# Top.net
KiCad netlist of a schematic drawn in Altium Designer
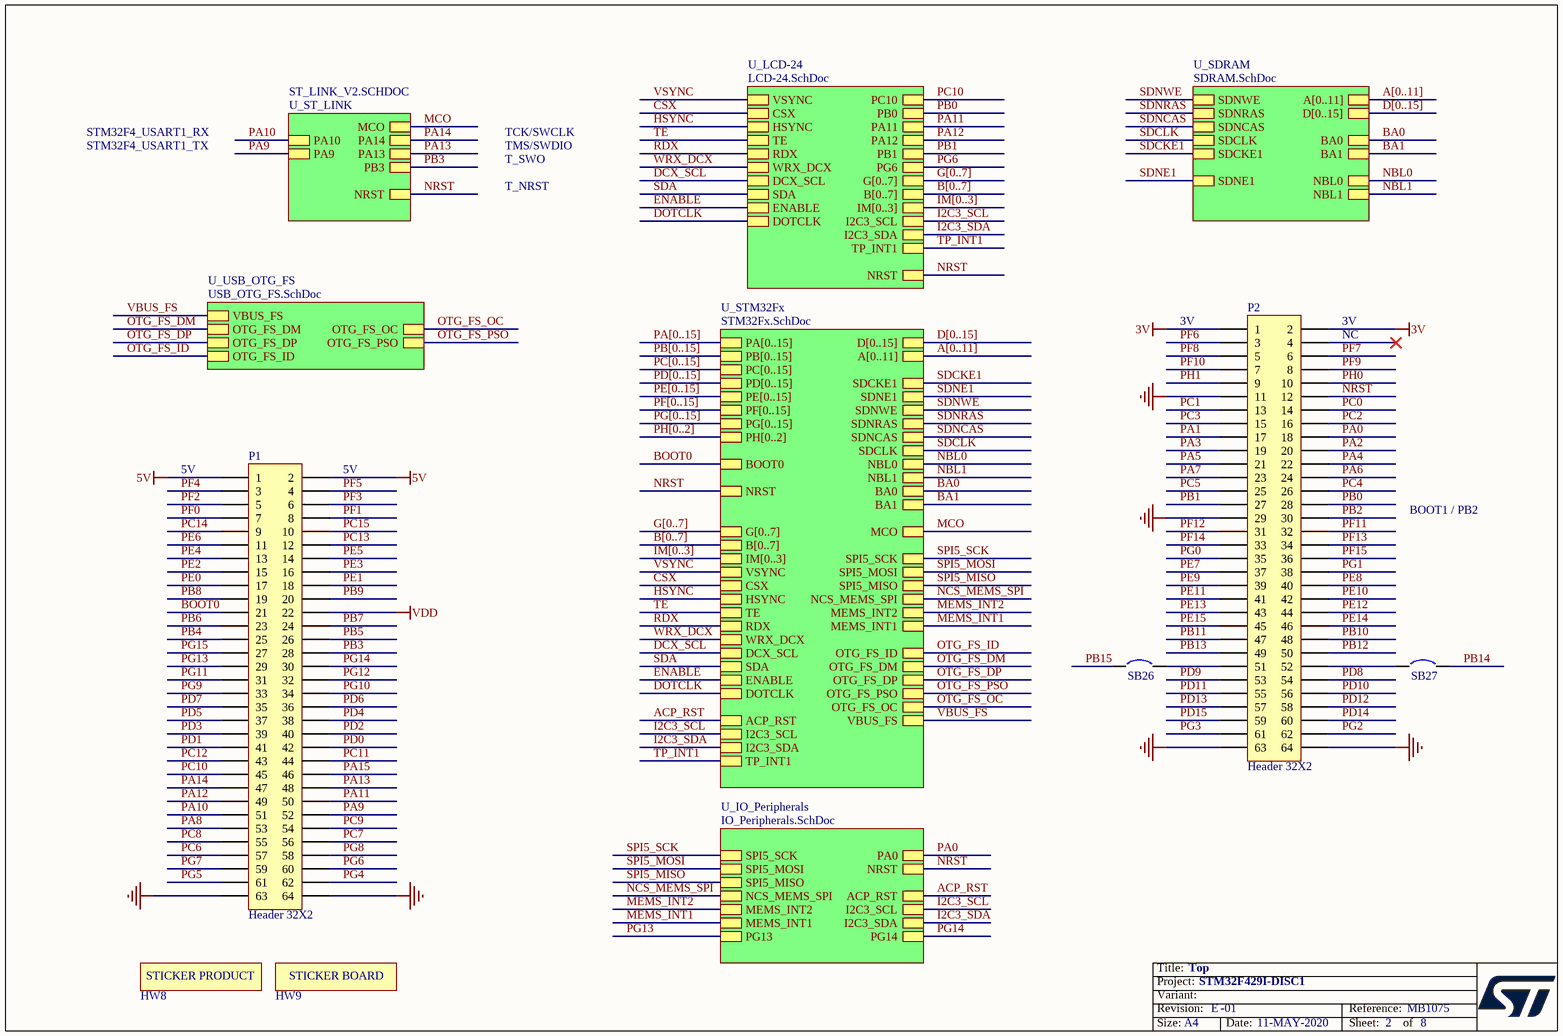
[diagram p0: Top.SchDoc]

(export (version "E")
  (design (tool "Eeschema 10.0.6"))
  (components
    (comp (ref "HW8") (value "STICKER_PRODUCT") (libsource (lib "MB1075") (part "STICKER_PRODUCT")))
    (comp (ref "HW9") (value "STICKER_BOARD") (libsource (lib "MB1075") (part "STICKER_BOARD")))
    (comp (ref "P1")
      (value "Header 32X2")
      (footprint "HDR2X32")
      (description "Header, 32-Pin, Dual row")
      (fields (field (name "PUBLISHER") "Altium Limited"))
      (libsource (lib "MCD_TOOLS") (part "Header 32X2"))
    )
    (comp (ref "P2")
      (value "Header 32X2")
      (footprint "HDR2X32")
      (description "Header, 32-Pin, Dual row")
      (fields (field (name "PUBLISHER") "Altium Limited"))
      (libsource (lib "MCD_TOOLS") (part "Header 32X2"))
    )
    (comp (ref "SB26")
      (value "Circuit Breaker")
      (footprint "JP2_SMD")
      (fields (field (name "PUBLISHER") "Altium Limited"))
      (libsource (lib "MCD_TOOLS") (part "Circuit Breaker"))
    )
    (comp (ref "SB27")
      (value "Circuit Breaker")
      (footprint "JP2_SMD")
      (fields (field (name "PUBLISHER") "Altium Limited"))
      (libsource (lib "MCD_TOOLS") (part "Circuit Breaker"))
    )
  )
  (nets
    (net (code "54") (name "/BOOT0") (class "Default")
      (node (ref "P1") (pin "21") (pinfunction "21_21") (pintype "passive"))
    )
    (net (code "72") (name "/NRST") (class "Default")
      (node (ref "P2") (pin "12") (pinfunction "12_12") (pintype "passive"))
    )
    (net (code "78") (name "/PA0") (class "Default")
      (node (ref "P2") (pin "18") (pinfunction "18_18") (pintype "passive"))
    )
    (net (code "79") (name "/PA1") (class "Default")
      (node (ref "P2") (pin "17") (pinfunction "17_17") (pintype "passive"))
    )
    (net (code "80") (name "/PA2") (class "Default")
      (node (ref "P2") (pin "20") (pinfunction "20_20") (pintype "passive"))
    )
    (net (code "81") (name "/PA3") (class "Default")
      (node (ref "P2") (pin "19") (pinfunction "19_19") (pintype "passive"))
    )
    (net (code "82") (name "/PA4") (class "Default")
      (node (ref "P2") (pin "22") (pinfunction "22_22") (pintype "passive"))
    )
    (net (code "83") (name "/PA5") (class "Default")
      (node (ref "P2") (pin "21") (pinfunction "21_21") (pintype "passive"))
    )
    (net (code "84") (name "/PA6") (class "Default")
      (node (ref "P2") (pin "24") (pinfunction "24_24") (pintype "passive"))
    )
    (net (code "85") (name "/PA7") (class "Default")
      (node (ref "P2") (pin "23") (pinfunction "23_23") (pintype "passive"))
    )
    (net (code "86") (name "/PA8") (class "Default")
      (node (ref "P1") (pin "53") (pinfunction "53_53") (pintype "passive"))
    )
    (net (code "87") (name "/PA9") (class "Default")
      (node (ref "P1") (pin "52") (pinfunction "52_52") (pintype "passive"))
    )
    (net (code "88") (name "/PA10") (class "Default")
      (node (ref "P1") (pin "51") (pinfunction "51_51") (pintype "passive"))
    )
    (net (code "89") (name "/PA11") (class "Default")
      (node (ref "P1") (pin "50") (pinfunction "50_50") (pintype "passive"))
    )
    (net (code "90") (name "/PA12") (class "Default")
      (node (ref "P1") (pin "49") (pinfunction "49_49") (pintype "passive"))
    )
    (net (code "91") (name "/PA13") (class "Default")
      (node (ref "P1") (pin "48") (pinfunction "48_48") (pintype "passive"))
    )
    (net (code "92") (name "/PA14") (class "Default")
      (node (ref "P1") (pin "47") (pinfunction "47_47") (pintype "passive"))
    )
    (net (code "93") (name "/PA15") (class "Default")
      (node (ref "P1") (pin "46") (pinfunction "46_46") (pintype "passive"))
    )
    (net (code "95") (name "/PB0") (class "Default")
      (node (ref "P2") (pin "28") (pinfunction "28_28") (pintype "passive"))
    )
    (net (code "96") (name "/PB1") (class "Default")
      (node (ref "P2") (pin "27") (pinfunction "27_27") (pintype "passive"))
    )
    (net (code "97") (name "/PB2") (class "Default")
      (node (ref "P2") (pin "30") (pinfunction "30_30") (pintype "passive"))
    )
    (net (code "98") (name "/PB3") (class "Default")
      (node (ref "P1") (pin "28") (pinfunction "28_28") (pintype "passive"))
    )
    (net (code "99") (name "/PB4") (class "Default")
      (node (ref "P1") (pin "25") (pinfunction "25_25") (pintype "passive"))
    )
    (net (code "100") (name "/PB5") (class "Default")
      (node (ref "P1") (pin "26") (pinfunction "26_26") (pintype "passive"))
    )
    (net (code "101") (name "/PB6") (class "Default")
      (node (ref "P1") (pin "23") (pinfunction "23_23") (pintype "passive"))
    )
    (net (code "102") (name "/PB7") (class "Default")
      (node (ref "P1") (pin "24") (pinfunction "24_24") (pintype "passive"))
    )
    (net (code "103") (name "/PB8") (class "Default")
      (node (ref "P1") (pin "19") (pinfunction "19_19") (pintype "passive"))
    )
    (net (code "104") (name "/PB9") (class "Default")
      (node (ref "P1") (pin "20") (pinfunction "20_20") (pintype "passive"))
    )
    (net (code "105") (name "/PB10") (class "Default")
      (node (ref "P2") (pin "48") (pinfunction "48_48") (pintype "passive"))
    )
    (net (code "106") (name "/PB11") (class "Default")
      (node (ref "P2") (pin "47") (pinfunction "47_47") (pintype "passive"))
    )
    (net (code "107") (name "/PB12") (class "Default")
      (node (ref "P2") (pin "50") (pinfunction "50_50") (pintype "passive"))
    )
    (net (code "108") (name "/PB13") (class "Default")
      (node (ref "P2") (pin "49") (pinfunction "49_49") (pintype "passive"))
    )
    (net (code "109") (name "/PB14") (class "Default")
      (node (ref "SB27") (pin "2") (pinfunction "2_2") (pintype "passive"))
    )
    (net (code "110") (name "/PB15") (class "Default")
      (node (ref "SB26") (pin "1") (pinfunction "1_1") (pintype "passive"))
    )
    (net (code "112") (name "/PC0") (class "Default")
      (node (ref "P2") (pin "14") (pinfunction "14_14") (pintype "passive"))
    )
    (net (code "113") (name "/PC1") (class "Default")
      (node (ref "P2") (pin "13") (pinfunction "13_13") (pintype "passive"))
    )
    (net (code "114") (name "/PC2") (class "Default")
      (node (ref "P2") (pin "16") (pinfunction "16_16") (pintype "passive"))
    )
    (net (code "115") (name "/PC3") (class "Default")
      (node (ref "P2") (pin "15") (pinfunction "15_15") (pintype "passive"))
    )
    (net (code "116") (name "/PC4") (class "Default")
      (node (ref "P2") (pin "26") (pinfunction "26_26") (pintype "passive"))
    )
    (net (code "117") (name "/PC5") (class "Default")
      (node (ref "P2") (pin "25") (pinfunction "25_25") (pintype "passive"))
    )
    (net (code "118") (name "/PC6") (class "Default")
      (node (ref "P1") (pin "57") (pinfunction "57_57") (pintype "passive"))
    )
    (net (code "119") (name "/PC7") (class "Default")
      (node (ref "P1") (pin "56") (pinfunction "56_56") (pintype "passive"))
    )
    (net (code "120") (name "/PC8") (class "Default")
      (node (ref "P1") (pin "55") (pinfunction "55_55") (pintype "passive"))
    )
    (net (code "121") (name "/PC9") (class "Default")
      (node (ref "P1") (pin "54") (pinfunction "54_54") (pintype "passive"))
    )
    (net (code "122") (name "/PC10") (class "Default")
      (node (ref "P1") (pin "45") (pinfunction "45_45") (pintype "passive"))
    )
    (net (code "123") (name "/PC11") (class "Default")
      (node (ref "P1") (pin "44") (pinfunction "44_44") (pintype "passive"))
    )
    (net (code "124") (name "/PC12") (class "Default")
      (node (ref "P1") (pin "43") (pinfunction "43_43") (pintype "passive"))
    )
    (net (code "125") (name "/PC13") (class "Default")
      (node (ref "P1") (pin "12") (pinfunction "12_12") (pintype "passive"))
    )
    (net (code "126") (name "/PC14") (class "Default")
      (node (ref "P1") (pin "9") (pinfunction "9_9") (pintype "passive"))
    )
    (net (code "127") (name "/PC15") (class "Default")
      (node (ref "P1") (pin "10") (pinfunction "10_10") (pintype "passive"))
    )
    (net (code "129") (name "/PD0") (class "Default")
      (node (ref "P1") (pin "42") (pinfunction "42_42") (pintype "passive"))
    )
    (net (code "130") (name "/PD1") (class "Default")
      (node (ref "P1") (pin "41") (pinfunction "41_41") (pintype "passive"))
    )
    (net (code "131") (name "/PD2") (class "Default")
      (node (ref "P1") (pin "40") (pinfunction "40_40") (pintype "passive"))
    )
    (net (code "132") (name "/PD3") (class "Default")
      (node (ref "P1") (pin "39") (pinfunction "39_39") (pintype "passive"))
    )
    (net (code "133") (name "/PD4") (class "Default")
      (node (ref "P1") (pin "38") (pinfunction "38_38") (pintype "passive"))
    )
    (net (code "134") (name "/PD5") (class "Default")
      (node (ref "P1") (pin "37") (pinfunction "37_37") (pintype "passive"))
    )
    (net (code "135") (name "/PD6") (class "Default")
      (node (ref "P1") (pin "36") (pinfunction "36_36") (pintype "passive"))
    )
    (net (code "136") (name "/PD7") (class "Default")
      (node (ref "P1") (pin "35") (pinfunction "35_35") (pintype "passive"))
    )
    (net (code "137") (name "/PD8") (class "Default")
      (node (ref "P2") (pin "54") (pinfunction "54_54") (pintype "passive"))
    )
    (net (code "138") (name "/PD9") (class "Default")
      (node (ref "P2") (pin "53") (pinfunction "53_53") (pintype "passive"))
    )
    (net (code "139") (name "/PD10") (class "Default")
      (node (ref "P2") (pin "56") (pinfunction "56_56") (pintype "passive"))
    )
    (net (code "140") (name "/PD11") (class "Default")
      (node (ref "P2") (pin "55") (pinfunction "55_55") (pintype "passive"))
    )
    (net (code "141") (name "/PD12") (class "Default")
      (node (ref "P2") (pin "58") (pinfunction "58_58") (pintype "passive"))
    )
    (net (code "142") (name "/PD13") (class "Default")
      (node (ref "P2") (pin "57") (pinfunction "57_57") (pintype "passive"))
    )
    (net (code "143") (name "/PD14") (class "Default")
      (node (ref "P2") (pin "60") (pinfunction "60_60") (pintype "passive"))
    )
    (net (code "144") (name "/PD15") (class "Default")
      (node (ref "P2") (pin "59") (pinfunction "59_59") (pintype "passive"))
    )
    (net (code "146") (name "/PE0") (class "Default")
      (node (ref "P1") (pin "17") (pinfunction "17_17") (pintype "passive"))
    )
    (net (code "147") (name "/PE1") (class "Default")
      (node (ref "P1") (pin "18") (pinfunction "18_18") (pintype "passive"))
    )
    (net (code "148") (name "/PE2") (class "Default")
      (node (ref "P1") (pin "15") (pinfunction "15_15") (pintype "passive"))
    )
    (net (code "149") (name "/PE3") (class "Default")
      (node (ref "P1") (pin "16") (pinfunction "16_16") (pintype "passive"))
    )
    (net (code "150") (name "/PE4") (class "Default")
      (node (ref "P1") (pin "13") (pinfunction "13_13") (pintype "passive"))
    )
    (net (code "151") (name "/PE5") (class "Default")
      (node (ref "P1") (pin "14") (pinfunction "14_14") (pintype "passive"))
    )
    (net (code "152") (name "/PE6") (class "Default")
      (node (ref "P1") (pin "11") (pinfunction "11_11") (pintype "passive"))
    )
    (net (code "153") (name "/PE7") (class "Default")
      (node (ref "P2") (pin "37") (pinfunction "37_37") (pintype "passive"))
    )
    (net (code "154") (name "/PE8") (class "Default")
      (node (ref "P2") (pin "40") (pinfunction "40_40") (pintype "passive"))
    )
    (net (code "155") (name "/PE9") (class "Default")
      (node (ref "P2") (pin "39") (pinfunction "39_39") (pintype "passive"))
    )
    (net (code "156") (name "/PE10") (class "Default")
      (node (ref "P2") (pin "42") (pinfunction "42_42") (pintype "passive"))
    )
    (net (code "157") (name "/PE11") (class "Default")
      (node (ref "P2") (pin "41") (pinfunction "41_41") (pintype "passive"))
    )
    (net (code "158") (name "/PE12") (class "Default")
      (node (ref "P2") (pin "44") (pinfunction "44_44") (pintype "passive"))
    )
    (net (code "159") (name "/PE13") (class "Default")
      (node (ref "P2") (pin "43") (pinfunction "43_43") (pintype "passive"))
    )
    (net (code "160") (name "/PE14") (class "Default")
      (node (ref "P2") (pin "46") (pinfunction "46_46") (pintype "passive"))
    )
    (net (code "161") (name "/PE15") (class "Default")
      (node (ref "P2") (pin "45") (pinfunction "45_45") (pintype "passive"))
    )
    (net (code "163") (name "/PF0") (class "Default")
      (node (ref "P1") (pin "7") (pinfunction "7_7") (pintype "passive"))
    )
    (net (code "164") (name "/PF1") (class "Default")
      (node (ref "P1") (pin "8") (pinfunction "8_8") (pintype "passive"))
    )
    (net (code "165") (name "/PF2") (class "Default")
      (node (ref "P1") (pin "5") (pinfunction "5_5") (pintype "passive"))
    )
    (net (code "166") (name "/PF3") (class "Default")
      (node (ref "P1") (pin "6") (pinfunction "6_6") (pintype "passive"))
    )
    (net (code "167") (name "/PF4") (class "Default")
      (node (ref "P1") (pin "3") (pinfunction "3_3") (pintype "passive"))
    )
    (net (code "168") (name "/PF5") (class "Default")
      (node (ref "P1") (pin "4") (pinfunction "4_4") (pintype "passive"))
    )
    (net (code "169") (name "/PF6") (class "Default")
      (node (ref "P2") (pin "3") (pinfunction "3_3") (pintype "passive"))
    )
    (net (code "170") (name "/PF7") (class "Default")
      (node (ref "P2") (pin "6") (pinfunction "6_6") (pintype "passive"))
    )
    (net (code "171") (name "/PF8") (class "Default")
      (node (ref "P2") (pin "5") (pinfunction "5_5") (pintype "passive"))
    )
    (net (code "172") (name "/PF9") (class "Default")
      (node (ref "P2") (pin "8") (pinfunction "8_8") (pintype "passive"))
    )
    (net (code "173") (name "/PF10") (class "Default")
      (node (ref "P2") (pin "7") (pinfunction "7_7") (pintype "passive"))
    )
    (net (code "174") (name "/PF11") (class "Default")
      (node (ref "P2") (pin "32") (pinfunction "32_32") (pintype "passive"))
    )
    (net (code "175") (name "/PF12") (class "Default")
      (node (ref "P2") (pin "31") (pinfunction "31_31") (pintype "passive"))
    )
    (net (code "176") (name "/PF13") (class "Default")
      (node (ref "P2") (pin "34") (pinfunction "34_34") (pintype "passive"))
    )
    (net (code "177") (name "/PF14") (class "Default")
      (node (ref "P2") (pin "33") (pinfunction "33_33") (pintype "passive"))
    )
    (net (code "178") (name "/PF15") (class "Default")
      (node (ref "P2") (pin "36") (pinfunction "36_36") (pintype "passive"))
    )
    (net (code "180") (name "/PG0") (class "Default")
      (node (ref "P2") (pin "35") (pinfunction "35_35") (pintype "passive"))
    )
    (net (code "181") (name "/PG1") (class "Default")
      (node (ref "P2") (pin "38") (pinfunction "38_38") (pintype "passive"))
    )
    (net (code "182") (name "/PG2") (class "Default")
      (node (ref "P2") (pin "62") (pinfunction "62_62") (pintype "passive"))
    )
    (net (code "183") (name "/PG3") (class "Default")
      (node (ref "P2") (pin "61") (pinfunction "61_61") (pintype "passive"))
    )
    (net (code "184") (name "/PG4") (class "Default")
      (node (ref "P1") (pin "62") (pinfunction "62_62") (pintype "passive"))
    )
    (net (code "185") (name "/PG5") (class "Default")
      (node (ref "P1") (pin "61") (pinfunction "61_61") (pintype "passive"))
    )
    (net (code "186") (name "/PG6") (class "Default")
      (node (ref "P1") (pin "60") (pinfunction "60_60") (pintype "passive"))
    )
    (net (code "187") (name "/PG7") (class "Default")
      (node (ref "P1") (pin "59") (pinfunction "59_59") (pintype "passive"))
    )
    (net (code "188") (name "/PG8") (class "Default")
      (node (ref "P1") (pin "58") (pinfunction "58_58") (pintype "passive"))
    )
    (net (code "189") (name "/PG9") (class "Default")
      (node (ref "P1") (pin "33") (pinfunction "33_33") (pintype "passive"))
    )
    (net (code "190") (name "/PG10") (class "Default")
      (node (ref "P1") (pin "34") (pinfunction "34_34") (pintype "passive"))
    )
    (net (code "191") (name "/PG11") (class "Default")
      (node (ref "P1") (pin "31") (pinfunction "31_31") (pintype "passive"))
    )
    (net (code "192") (name "/PG12") (class "Default")
      (node (ref "P1") (pin "32") (pinfunction "32_32") (pintype "passive"))
    )
    (net (code "193") (name "/PG13") (class "Default")
      (node (ref "P1") (pin "29") (pinfunction "29_29") (pintype "passive"))
    )
    (net (code "194") (name "/PG14") (class "Default")
      (node (ref "P1") (pin "30") (pinfunction "30_30") (pintype "passive"))
    )
    (net (code "195") (name "/PG15") (class "Default")
      (node (ref "P1") (pin "27") (pinfunction "27_27") (pintype "passive"))
    )
    (net (code "197") (name "/PH0") (class "Default")
      (node (ref "P2") (pin "10") (pinfunction "10_10") (pintype "passive"))
    )
    (net (code "198") (name "/PH1") (class "Default")
      (node (ref "P2") (pin "9") (pinfunction "9_9") (pintype "passive"))
    )
    (net (code "216") (name "3V") (class "Default")
      (node (ref "P2") (pin "1") (pinfunction "1_1") (pintype "passive"))
      (node (ref "P2") (pin "2") (pinfunction "2_2") (pintype "passive"))
    )
    (net (code "217") (name "5V") (class "Default")
      (node (ref "P1") (pin "1") (pinfunction "1_1") (pintype "passive"))
      (node (ref "P1") (pin "2") (pinfunction "2_2") (pintype "passive"))
    )
    (net (code "218") (name "GND") (class "Default")
      (node (ref "P1") (pin "63") (pinfunction "63_63") (pintype "passive"))
      (node (ref "P1") (pin "64") (pinfunction "64_64") (pintype "passive"))
      (node (ref "P2") (pin "11") (pinfunction "11_11") (pintype "passive"))
      (node (ref "P2") (pin "29") (pinfunction "29_29") (pintype "passive"))
      (node (ref "P2") (pin "63") (pinfunction "63_63") (pintype "passive"))
      (node (ref "P2") (pin "64") (pinfunction "64_64") (pintype "passive"))
    )
    (net (code "219") (name "Net-(P2-Pad51)") (class "Default")
      (node (ref "P2") (pin "51") (pinfunction "51_51") (pintype "passive"))
      (node (ref "SB26") (pin "2") (pinfunction "2_2") (pintype "passive"))
    )
    (net (code "220") (name "Net-(P2-Pad52)") (class "Default")
      (node (ref "P2") (pin "52") (pinfunction "52_52") (pintype "passive"))
      (node (ref "SB27") (pin "1") (pinfunction "1_1") (pintype "passive"))
    )
    (net (code "221") (name "VDD") (class "Default")
      (node (ref "P1") (pin "22") (pinfunction "22_22") (pintype "passive"))
    )
    (net (code "222") (name "unconnected-(P2-Pad4)") (class "Default")
      (node (ref "P2") (pin "4") (pinfunction "4_4") (pintype "passive+no_connect"))
    )
  )
)
